# G27InterfaceBoard.net
KiCad netlist of a schematic drawn in EAGLE
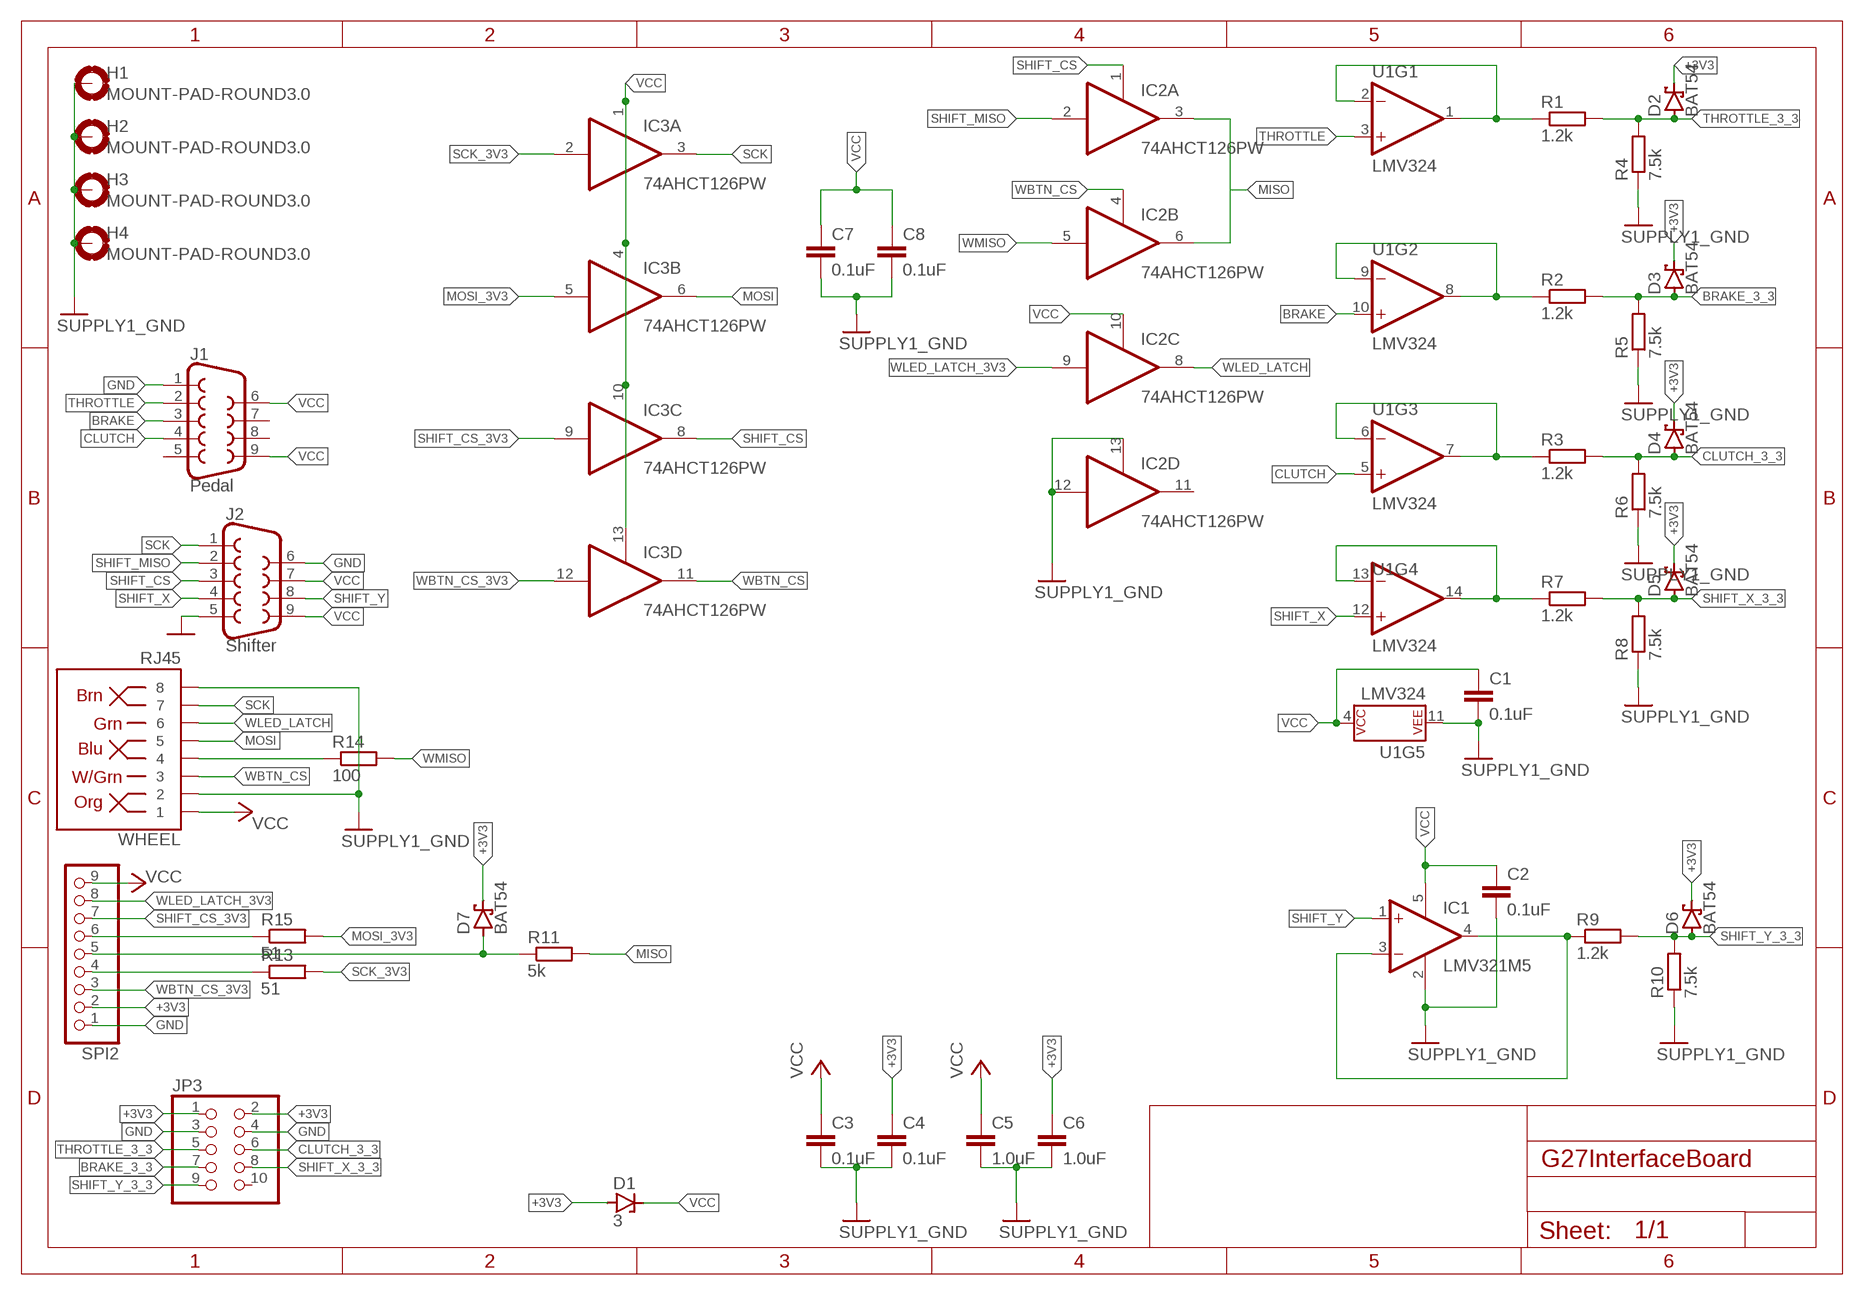
[diagram p0: schematic, sheet 1]

(export (version "E")
  (design (tool "Eeschema 10.0.6"))
  (components
    (comp (ref "C1")
      (value "0.1uF")
      (footprint "eagle-import:RESISTOR_C0603")
      (libsource (lib "eagle-import") (part "RESISTOR_C-EUC0603"))
    )
    (comp (ref "C2")
      (value "0.1uF")
      (footprint "eagle-import:RESISTOR_C0603")
      (libsource (lib "eagle-import") (part "RESISTOR_C-EUC0603"))
    )
    (comp (ref "C3")
      (value "0.1uF")
      (footprint "eagle-import:C0805")
      (libsource (lib "eagle-import") (part "C-EUC0805"))
    )
    (comp (ref "C4")
      (value "0.1uF")
      (footprint "eagle-import:C0805")
      (libsource (lib "eagle-import") (part "C-EUC0805"))
    )
    (comp (ref "C5")
      (value "1.0uF")
      (footprint "eagle-import:C0805")
      (libsource (lib "eagle-import") (part "C-EUC0805"))
    )
    (comp (ref "C6")
      (value "1.0uF")
      (footprint "eagle-import:C0805")
      (libsource (lib "eagle-import") (part "C-EUC0805"))
    )
    (comp (ref "C7")
      (value "0.1uF")
      (footprint "eagle-import:C0603")
      (libsource (lib "eagle-import") (part "C-EUC0603"))
    )
    (comp (ref "C8")
      (value "0.1uF")
      (footprint "eagle-import:C0603")
      (libsource (lib "eagle-import") (part "C-EUC0603"))
    )
    (comp (ref "D1")
      (value "3")
      (footprint "eagle-import:SOT23")
      (fields (field (name "SPICEPREFIX") "D"))
      (libsource (lib "eagle-import") (part "ZENER-DIODESOT23"))
    )
    (comp (ref "D2")
      (value "BAT54")
      (footprint "eagle-import:SOT23")
      (libsource (lib "eagle-import") (part "BAT54"))
    )
    (comp (ref "D3")
      (value "BAT54")
      (footprint "eagle-import:SOT23")
      (libsource (lib "eagle-import") (part "BAT54"))
    )
    (comp (ref "D4")
      (value "BAT54")
      (footprint "eagle-import:SOT23")
      (libsource (lib "eagle-import") (part "BAT54"))
    )
    (comp (ref "D5")
      (value "BAT54")
      (footprint "eagle-import:SOT23")
      (libsource (lib "eagle-import") (part "BAT54"))
    )
    (comp (ref "D6")
      (value "BAT54")
      (footprint "eagle-import:SOT23")
      (libsource (lib "eagle-import") (part "BAT54"))
    )
    (comp (ref "D7")
      (value "BAT54")
      (footprint "eagle-import:SOT23")
      (libsource (lib "eagle-import") (part "BAT54"))
    )
    (comp (ref "H1")
      (value "MOUNT-PAD-ROUND3.0")
      (footprint "eagle-import:3,0-PAD")
      (libsource (lib "eagle-import") (part "MOUNT-PAD-ROUND3.0"))
    )
    (comp (ref "H2")
      (value "MOUNT-PAD-ROUND3.0")
      (footprint "eagle-import:3,0-PAD")
      (libsource (lib "eagle-import") (part "MOUNT-PAD-ROUND3.0"))
    )
    (comp (ref "H3")
      (value "MOUNT-PAD-ROUND3.0")
      (footprint "eagle-import:3,0-PAD")
      (libsource (lib "eagle-import") (part "MOUNT-PAD-ROUND3.0"))
    )
    (comp (ref "H4")
      (value "MOUNT-PAD-ROUND3.0")
      (footprint "eagle-import:3,0-PAD")
      (libsource (lib "eagle-import") (part "MOUNT-PAD-ROUND3.0"))
    )
    (comp (ref "IC1")
      (value "LMV321M5")
      (footprint "eagle-import:SOT23-5")
      (libsource (lib "eagle-import") (part "LMV321?M5"))
    )
    (comp (ref "IC2")
      (value "74AHCT126PW")
      (footprint "eagle-import:TSSOP14")
      (libsource (lib "eagle-import") (part "74126PWAHCT"))
    )
    (comp (ref "IC3")
      (value "74AHCT126PW")
      (footprint "eagle-import:TSSOP14")
      (libsource (lib "eagle-import") (part "74126PWAHCT"))
    )
    (comp (ref "J1")
      (value "Pedal")
      (footprint "eagle-import:DB9")
      (libsource (lib "eagle-import") (part "DB9FEMALE"))
    )
    (comp (ref "J2")
      (value "Shifter")
      (footprint "eagle-import:DB9_MALE")
      (libsource (lib "eagle-import") (part "DB9MALE"))
    )
    (comp (ref "JP3")
      (value "PINHEAD_PINHD-2X5")
      (footprint "eagle-import:PINHEAD_2X05")
      (libsource (lib "eagle-import") (part "PINHEAD_PINHD-2X5"))
    )
    (comp (ref "R1")
      (value "1.2k")
      (footprint "eagle-import:R0603")
      (libsource (lib "eagle-import") (part "R-EU_R0603"))
    )
    (comp (ref "R2")
      (value "1.2k")
      (footprint "eagle-import:R0603")
      (libsource (lib "eagle-import") (part "R-EU_R0603"))
    )
    (comp (ref "R3")
      (value "1.2k")
      (footprint "eagle-import:R0603")
      (libsource (lib "eagle-import") (part "R-EU_R0603"))
    )
    (comp (ref "R4")
      (value "7.5k")
      (footprint "eagle-import:R0603")
      (libsource (lib "eagle-import") (part "R-EU_R0603"))
    )
    (comp (ref "R5")
      (value "7.5k")
      (footprint "eagle-import:R0603")
      (libsource (lib "eagle-import") (part "R-EU_R0603"))
    )
    (comp (ref "R6")
      (value "7.5k")
      (footprint "eagle-import:R0603")
      (libsource (lib "eagle-import") (part "R-EU_R0603"))
    )
    (comp (ref "R7")
      (value "1.2k")
      (footprint "eagle-import:R0603")
      (libsource (lib "eagle-import") (part "R-EU_R0603"))
    )
    (comp (ref "R8")
      (value "7.5k")
      (footprint "eagle-import:R0603")
      (libsource (lib "eagle-import") (part "R-EU_R0603"))
    )
    (comp (ref "R9")
      (value "1.2k")
      (footprint "eagle-import:R0603")
      (libsource (lib "eagle-import") (part "R-EU_R0603"))
    )
    (comp (ref "R10")
      (value "7.5k")
      (footprint "eagle-import:R0603")
      (libsource (lib "eagle-import") (part "R-EU_R0603"))
    )
    (comp (ref "R11")
      (value "5k")
      (footprint "eagle-import:R0603")
      (libsource (lib "eagle-import") (part "R-EU_R0603"))
    )
    (comp (ref "R13")
      (value "51")
      (footprint "eagle-import:R0603")
      (libsource (lib "eagle-import") (part "R-EU_R0603"))
    )
    (comp (ref "R14")
      (value "100")
      (footprint "eagle-import:R0603")
      (libsource (lib "eagle-import") (part "R-EU_R0603"))
    )
    (comp (ref "R15")
      (value "51")
      (footprint "eagle-import:R0603")
      (libsource (lib "eagle-import") (part "R-EU_R0603"))
    )
    (comp (ref "SPI2")
      (value "PINHD-1X9")
      (footprint "eagle-import:1X09")
      (libsource (lib "eagle-import") (part "PINHD-1X9"))
    )
    (comp (ref "U1")
      (value "LMV324")
      (footprint "eagle-import:SO14")
      (libsource (lib "eagle-import") (part "LMV324"))
    )
    (comp (ref "WHEEL")
      (value "RJ45")
      (footprint "eagle-import:RJ45-8")
      (libsource (lib "eagle-import") (part "RJ45-8"))
    )
  )
  (nets
    (net (code "1") (name "+3V3") (class "Default")
      (node (ref "C4") (pin "1") (pinfunction "1_1") (pintype "passive"))
      (node (ref "C6") (pin "1") (pinfunction "1_1") (pintype "passive"))
      (node (ref "D1") (pin "1") (pinfunction "A_1") (pintype "passive"))
      (node (ref "D2") (pin "3") (pinfunction "C_3") (pintype "passive"))
      (node (ref "D3") (pin "3") (pinfunction "C_3") (pintype "passive"))
      (node (ref "D4") (pin "3") (pinfunction "C_3") (pintype "passive"))
      (node (ref "D5") (pin "3") (pinfunction "C_3") (pintype "passive"))
      (node (ref "D6") (pin "3") (pinfunction "C_3") (pintype "passive"))
      (node (ref "D7") (pin "3") (pinfunction "C_3") (pintype "passive"))
      (node (ref "JP3") (pin "1") (pinfunction "1_1") (pintype "passive"))
      (node (ref "JP3") (pin "2") (pinfunction "2_2") (pintype "passive"))
      (node (ref "SPI2") (pin "2") (pinfunction "2_2") (pintype "passive"))
    )
    (net (code "2") (name "BRAKE") (class "Default")
      (node (ref "J1") (pin "3") (pinfunction "3_3") (pintype "passive"))
      (node (ref "U1") (pin "10") (pinfunction "+IN_10") (pintype "input"))
    )
    (net (code "3") (name "BRAKE_3_3") (class "Default")
      (node (ref "D3") (pin "1") (pinfunction "A_1") (pintype "passive"))
      (node (ref "JP3") (pin "7") (pinfunction "7_7") (pintype "passive"))
      (node (ref "R2") (pin "2") (pinfunction "2_2") (pintype "passive"))
      (node (ref "R5") (pin "2") (pinfunction "2_2") (pintype "passive"))
    )
    (net (code "4") (name "CLUTCH") (class "Default")
      (node (ref "J1") (pin "4") (pinfunction "4_4") (pintype "passive"))
      (node (ref "U1") (pin "5") (pinfunction "+IN_5") (pintype "input"))
    )
    (net (code "5") (name "CLUTCH_3_3") (class "Default")
      (node (ref "D4") (pin "1") (pinfunction "A_1") (pintype "passive"))
      (node (ref "JP3") (pin "6") (pinfunction "6_6") (pintype "passive"))
      (node (ref "R3") (pin "2") (pinfunction "2_2") (pintype "passive"))
      (node (ref "R6") (pin "2") (pinfunction "2_2") (pintype "passive"))
    )
    (net (code "6") (name "GND") (class "Default")
      (node (ref "C1") (pin "2") (pinfunction "2_2") (pintype "passive"))
      (node (ref "C2") (pin "2") (pinfunction "2_2") (pintype "passive"))
      (node (ref "C3") (pin "2") (pinfunction "2_2") (pintype "passive"))
      (node (ref "C4") (pin "2") (pinfunction "2_2") (pintype "passive"))
      (node (ref "C5") (pin "2") (pinfunction "2_2") (pintype "passive"))
      (node (ref "C6") (pin "2") (pinfunction "2_2") (pintype "passive"))
      (node (ref "C7") (pin "2") (pinfunction "2_2") (pintype "passive"))
      (node (ref "C8") (pin "2") (pinfunction "2_2") (pintype "passive"))
      (node (ref "H1") (pin "B3,0") (pinfunction "MOUNT_B3,0") (pintype "passive"))
      (node (ref "H2") (pin "B3,0") (pinfunction "MOUNT_B3,0") (pintype "passive"))
      (node (ref "H3") (pin "B3,0") (pinfunction "MOUNT_B3,0") (pintype "passive"))
      (node (ref "H4") (pin "B3,0") (pinfunction "MOUNT_B3,0") (pintype "passive"))
      (node (ref "IC1") (pin "2") (pinfunction "V-_2") (pintype "power_in"))
      (node (ref "IC2") (pin "12") (pinfunction "I_12") (pintype "input"))
      (node (ref "IC2") (pin "13") (pinfunction "OE_13") (pintype "input"))
      (node (ref "J1") (pin "1") (pinfunction "1_1") (pintype "passive"))
      (node (ref "J2") (pin "5") (pinfunction "5_5") (pintype "passive"))
      (node (ref "J2") (pin "6") (pinfunction "6_6") (pintype "passive"))
      (node (ref "JP3") (pin "3") (pinfunction "3_3") (pintype "passive"))
      (node (ref "JP3") (pin "4") (pinfunction "4_4") (pintype "passive"))
      (node (ref "R10") (pin "1") (pinfunction "1_1") (pintype "passive"))
      (node (ref "R4") (pin "1") (pinfunction "1_1") (pintype "passive"))
      (node (ref "R5") (pin "1") (pinfunction "1_1") (pintype "passive"))
      (node (ref "R6") (pin "1") (pinfunction "1_1") (pintype "passive"))
      (node (ref "R8") (pin "1") (pinfunction "1_1") (pintype "passive"))
      (node (ref "SPI2") (pin "1") (pinfunction "1_1") (pintype "passive"))
      (node (ref "U1") (pin "11") (pinfunction "P$V-_11") (pintype "bidirectional"))
      (node (ref "WHEEL") (pin "2") (pinfunction "2_2") (pintype "bidirectional"))
      (node (ref "WHEEL") (pin "8") (pinfunction "8_8") (pintype "bidirectional"))
    )
    (net (code "7") (name "MISO") (class "Default")
      (node (ref "IC2") (pin "3") (pinfunction "O_3") (pintype "output"))
      (node (ref "IC2") (pin "6") (pinfunction "O_6") (pintype "output"))
      (node (ref "R11") (pin "2") (pinfunction "2_2") (pintype "passive"))
    )
    (net (code "8") (name "MOSI") (class "Default")
      (node (ref "IC3") (pin "6") (pinfunction "O_6") (pintype "output"))
      (node (ref "WHEEL") (pin "5") (pinfunction "5_5") (pintype "bidirectional"))
    )
    (net (code "9") (name "MOSI_3V3") (class "Default")
      (node (ref "IC3") (pin "5") (pinfunction "I_5") (pintype "input"))
      (node (ref "R15") (pin "2") (pinfunction "2_2") (pintype "passive"))
    )
    (net (code "10") (name "Net-(D7-A)") (class "Default")
      (node (ref "D7") (pin "1") (pinfunction "A_1") (pintype "passive"))
      (node (ref "R11") (pin "1") (pinfunction "1_1") (pintype "passive"))
      (node (ref "SPI2") (pin "5") (pinfunction "5_5") (pintype "passive"))
    )
    (net (code "11") (name "Net-(IC1--IN)") (class "Default")
      (node (ref "IC1") (pin "3") (pinfunction "-IN_3") (pintype "input"))
      (node (ref "IC1") (pin "4") (pinfunction "OUT_4") (pintype "output"))
      (node (ref "R9") (pin "1") (pinfunction "1_1") (pintype "passive"))
    )
    (net (code "12") (name "Net-(R13-Pad1)") (class "Default")
      (node (ref "R13") (pin "1") (pinfunction "1_1") (pintype "passive"))
      (node (ref "SPI2") (pin "4") (pinfunction "4_4") (pintype "passive"))
    )
    (net (code "13") (name "Net-(R14-Pad1)") (class "Default")
      (node (ref "R14") (pin "1") (pinfunction "1_1") (pintype "passive"))
      (node (ref "WHEEL") (pin "4") (pinfunction "4_4") (pintype "bidirectional"))
    )
    (net (code "14") (name "Net-(R15-Pad1)") (class "Default")
      (node (ref "R15") (pin "1") (pinfunction "1_1") (pintype "passive"))
      (node (ref "SPI2") (pin "6") (pinfunction "6_6") (pintype "passive"))
    )
    (net (code "15") (name "Net-(U1A--IN)") (class "Default")
      (node (ref "R1") (pin "1") (pinfunction "1_1") (pintype "passive"))
      (node (ref "U1") (pin "1") (pinfunction "OUT_1") (pintype "output"))
      (node (ref "U1") (pin "2") (pinfunction "-IN_2") (pintype "input"))
    )
    (net (code "16") (name "Net-(U1B--IN)") (class "Default")
      (node (ref "R2") (pin "1") (pinfunction "1_1") (pintype "passive"))
      (node (ref "U1") (pin "8") (pinfunction "OUT_8") (pintype "output"))
      (node (ref "U1") (pin "9") (pinfunction "-IN_9") (pintype "input"))
    )
    (net (code "17") (name "Net-(U1C--IN)") (class "Default")
      (node (ref "R3") (pin "1") (pinfunction "1_1") (pintype "passive"))
      (node (ref "U1") (pin "6") (pinfunction "-IN_6") (pintype "input"))
      (node (ref "U1") (pin "7") (pinfunction "OUT_7") (pintype "output"))
    )
    (net (code "18") (name "Net-(U1D--IN)") (class "Default")
      (node (ref "R7") (pin "1") (pinfunction "1_1") (pintype "passive"))
      (node (ref "U1") (pin "13") (pinfunction "-IN_13") (pintype "input"))
      (node (ref "U1") (pin "14") (pinfunction "OUT_14") (pintype "output"))
    )
    (net (code "19") (name "SCK") (class "Default")
      (node (ref "IC3") (pin "3") (pinfunction "O_3") (pintype "output"))
      (node (ref "J2") (pin "1") (pinfunction "1_1") (pintype "passive"))
      (node (ref "WHEEL") (pin "7") (pinfunction "7_7") (pintype "bidirectional"))
    )
    (net (code "20") (name "SCK_3V3") (class "Default")
      (node (ref "IC3") (pin "2") (pinfunction "I_2") (pintype "input"))
      (node (ref "R13") (pin "2") (pinfunction "2_2") (pintype "passive"))
    )
    (net (code "21") (name "SHIFT_CS") (class "Default")
      (node (ref "IC2") (pin "1") (pinfunction "OE_1") (pintype "input"))
      (node (ref "IC3") (pin "8") (pinfunction "O_8") (pintype "output"))
      (node (ref "J2") (pin "3") (pinfunction "3_3") (pintype "passive"))
    )
    (net (code "22") (name "SHIFT_CS_3V3") (class "Default")
      (node (ref "IC3") (pin "9") (pinfunction "I_9") (pintype "input"))
      (node (ref "SPI2") (pin "7") (pinfunction "7_7") (pintype "passive"))
    )
    (net (code "23") (name "SHIFT_MISO") (class "Default")
      (node (ref "IC2") (pin "2") (pinfunction "I_2") (pintype "input"))
      (node (ref "J2") (pin "2") (pinfunction "2_2") (pintype "passive"))
    )
    (net (code "24") (name "SHIFT_X") (class "Default")
      (node (ref "J2") (pin "4") (pinfunction "4_4") (pintype "passive"))
      (node (ref "U1") (pin "12") (pinfunction "+IN_12") (pintype "input"))
    )
    (net (code "25") (name "SHIFT_X_3_3") (class "Default")
      (node (ref "D5") (pin "1") (pinfunction "A_1") (pintype "passive"))
      (node (ref "JP3") (pin "8") (pinfunction "8_8") (pintype "passive"))
      (node (ref "R7") (pin "2") (pinfunction "2_2") (pintype "passive"))
      (node (ref "R8") (pin "2") (pinfunction "2_2") (pintype "passive"))
    )
    (net (code "26") (name "SHIFT_Y") (class "Default")
      (node (ref "IC1") (pin "1") (pinfunction "+IN_1") (pintype "input"))
      (node (ref "J2") (pin "8") (pinfunction "8_8") (pintype "passive"))
    )
    (net (code "27") (name "SHIFT_Y_3_3") (class "Default")
      (node (ref "D6") (pin "1") (pinfunction "A_1") (pintype "passive"))
      (node (ref "JP3") (pin "9") (pinfunction "9_9") (pintype "passive"))
      (node (ref "R10") (pin "2") (pinfunction "2_2") (pintype "passive"))
      (node (ref "R9") (pin "2") (pinfunction "2_2") (pintype "passive"))
    )
    (net (code "28") (name "THROTTLE") (class "Default")
      (node (ref "J1") (pin "2") (pinfunction "2_2") (pintype "passive"))
      (node (ref "U1") (pin "3") (pinfunction "+IN_3") (pintype "input"))
    )
    (net (code "29") (name "THROTTLE_3_3") (class "Default")
      (node (ref "D2") (pin "1") (pinfunction "A_1") (pintype "passive"))
      (node (ref "JP3") (pin "5") (pinfunction "5_5") (pintype "passive"))
      (node (ref "R1") (pin "2") (pinfunction "2_2") (pintype "passive"))
      (node (ref "R4") (pin "2") (pinfunction "2_2") (pintype "passive"))
    )
    (net (code "30") (name "VCC") (class "Default")
      (node (ref "C1") (pin "1") (pinfunction "1_1") (pintype "passive"))
      (node (ref "C2") (pin "1") (pinfunction "1_1") (pintype "passive"))
      (node (ref "C3") (pin "1") (pinfunction "1_1") (pintype "passive"))
      (node (ref "C5") (pin "1") (pinfunction "1_1") (pintype "passive"))
      (node (ref "C7") (pin "1") (pinfunction "1_1") (pintype "passive"))
      (node (ref "C8") (pin "1") (pinfunction "1_1") (pintype "passive"))
      (node (ref "D1") (pin "3") (pinfunction "C_3") (pintype "passive"))
      (node (ref "IC1") (pin "5") (pinfunction "V+_5") (pintype "power_in"))
      (node (ref "IC2") (pin "10") (pinfunction "OE_10") (pintype "input"))
      (node (ref "IC3") (pin "1") (pinfunction "OE_1") (pintype "input"))
      (node (ref "IC3") (pin "10") (pinfunction "OE_10") (pintype "input"))
      (node (ref "IC3") (pin "13") (pinfunction "OE_13") (pintype "input"))
      (node (ref "IC3") (pin "4") (pinfunction "OE_4") (pintype "input"))
      (node (ref "J1") (pin "6") (pinfunction "6_6") (pintype "passive"))
      (node (ref "J1") (pin "9") (pinfunction "9_9") (pintype "passive"))
      (node (ref "J2") (pin "7") (pinfunction "7_7") (pintype "passive"))
      (node (ref "J2") (pin "9") (pinfunction "9_9") (pintype "passive"))
      (node (ref "SPI2") (pin "9") (pinfunction "9_9") (pintype "passive"))
      (node (ref "U1") (pin "4") (pinfunction "P$V+_4") (pintype "bidirectional"))
      (node (ref "WHEEL") (pin "1") (pinfunction "1_1") (pintype "bidirectional"))
    )
    (net (code "31") (name "WBTN_CS") (class "Default")
      (node (ref "IC2") (pin "4") (pinfunction "OE_4") (pintype "input"))
      (node (ref "IC3") (pin "11") (pinfunction "O_11") (pintype "output"))
      (node (ref "WHEEL") (pin "3") (pinfunction "3_3") (pintype "bidirectional"))
    )
    (net (code "32") (name "WBTN_CS_3V3") (class "Default")
      (node (ref "IC3") (pin "12") (pinfunction "I_12") (pintype "input"))
      (node (ref "SPI2") (pin "3") (pinfunction "3_3") (pintype "passive"))
    )
    (net (code "33") (name "WLED_LATCH") (class "Default")
      (node (ref "IC2") (pin "8") (pinfunction "O_8") (pintype "output"))
      (node (ref "WHEEL") (pin "6") (pinfunction "6_6") (pintype "bidirectional"))
    )
    (net (code "34") (name "WLED_LATCH_3V3") (class "Default")
      (node (ref "IC2") (pin "9") (pinfunction "I_9") (pintype "input"))
      (node (ref "SPI2") (pin "8") (pinfunction "8_8") (pintype "passive"))
    )
    (net (code "35") (name "WMISO") (class "Default")
      (node (ref "IC2") (pin "5") (pinfunction "I_5") (pintype "input"))
      (node (ref "R14") (pin "2") (pinfunction "2_2") (pintype "passive"))
    )
    (net (code "36") (name "unconnected-(IC2D-O-Pad11)") (class "Default")
      (node (ref "IC2") (pin "11") (pinfunction "O_11") (pintype "output"))
    )
    (net (code "37") (name "unconnected-(J1-Pad5)") (class "Default")
      (node (ref "J1") (pin "5") (pinfunction "5_5") (pintype "passive"))
    )
    (net (code "38") (name "unconnected-(J1-Pad7)") (class "Default")
      (node (ref "J1") (pin "7") (pinfunction "7_7") (pintype "passive"))
    )
    (net (code "39") (name "unconnected-(J1-Pad8)") (class "Default")
      (node (ref "J1") (pin "8") (pinfunction "8_8") (pintype "passive"))
    )
    (net (code "40") (name "unconnected-(JP3-Pad10)") (class "Default")
      (node (ref "JP3") (pin "10") (pinfunction "10_10") (pintype "passive"))
    )
  )
)
